# espJhon.net
KiCad netlist of a schematic drawn in EAGLE
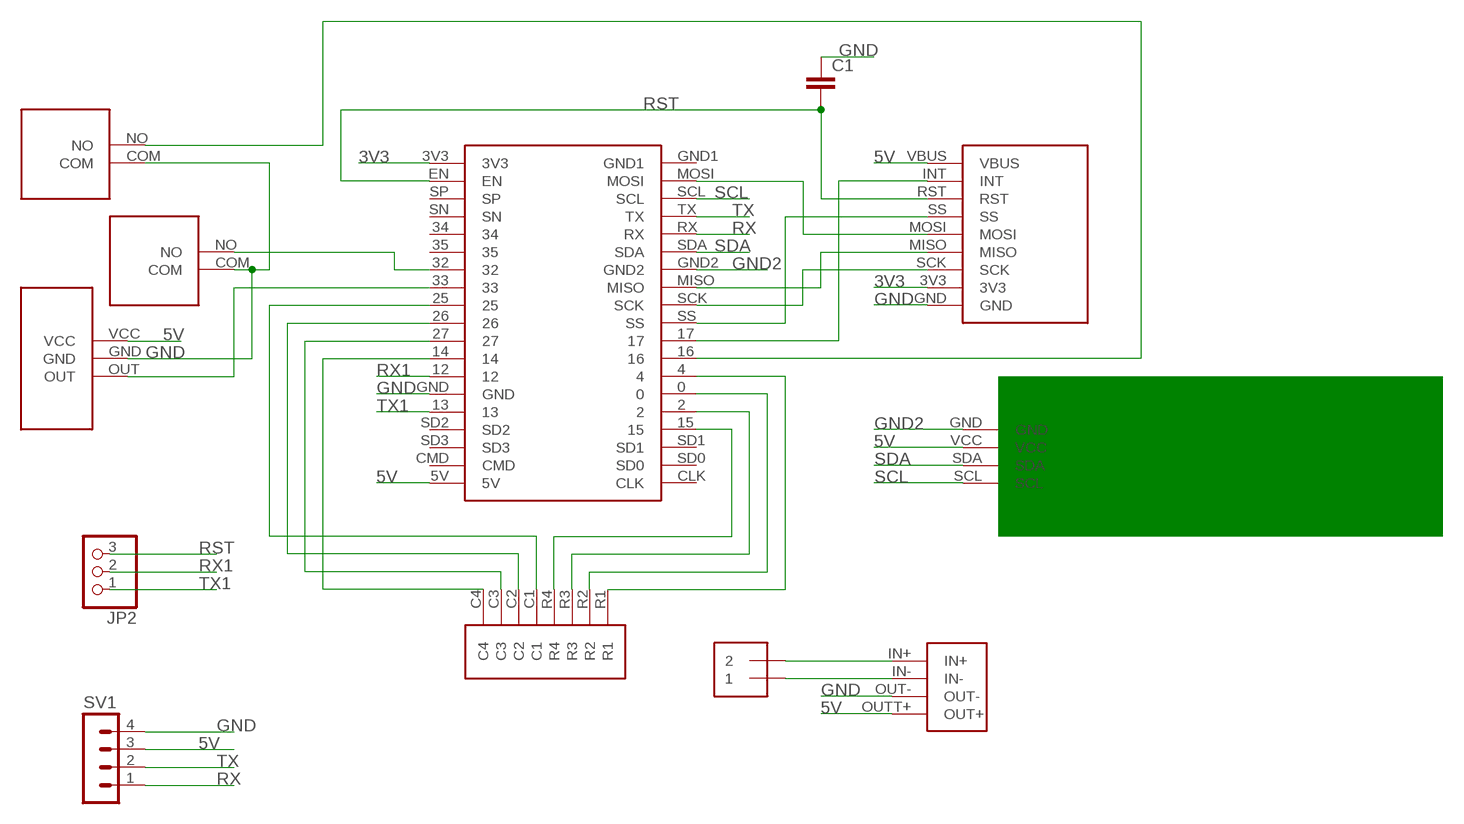
[diagram p0: schematic, sheet 1]

(export (version "E")
  (design (tool "Eeschema 10.0.6"))
  (components
    (comp (ref "C1")
      (value "C2.5/6")
      (footprint "eagle-import:C2.5-6")
      (libsource (lib "eagle-import") (part "C2.5/6"))
    )
    (comp (ref "J1")
      (value "1X2-3.5MM")
      (footprint "eagle-import:1X2-3.5MM")
      (libsource (lib "eagle-import") (part "1X2-3.5MM"))
    )
    (comp (ref "JP2")
      (value "PINHD-1X3")
      (footprint "eagle-import:1X03")
      (libsource (lib "eagle-import") (part "PINHD-1X3"))
    )
    (comp (ref "SV1")
      (value "MA04-1")
      (footprint "eagle-import:MA04-1")
      (libsource (lib "eagle-import") (part "MA04-1"))
    )
    (comp (ref "U$1")
      (value "XL4005E1")
      (footprint "eagle-import:XL4005E1")
      (libsource (lib "eagle-import") (part "XL4005E1"))
    )
    (comp (ref "U$2")
      (value "USB_HOST")
      (footprint "eagle-import:USB_HOST")
      (libsource (lib "eagle-import") (part "USB_HOST"))
    )
    (comp (ref "U$3")
      (value "ESP32_NEW")
      (footprint "eagle-import:ESP32_NEW")
      (libsource (lib "eagle-import") (part "ESP32_NEW"))
    )
    (comp (ref "U$4")
      (value "KEYPAD_4X4")
      (footprint "eagle-import:KEYPAD_4X4")
      (libsource (lib "eagle-import") (part "KEYPAD_4X4"))
    )
    (comp (ref "U$6")
      (value "LCD_I2C")
      (footprint "eagle-import:LCD_I2C")
      (libsource (lib "eagle-import") (part "LCD_I2C"))
    )
    (comp (ref "U$7")
      (value "IR_SENSOR")
      (footprint "eagle-import:IR_SENSOR")
      (libsource (lib "eagle-import") (part "IR_SENSOR"))
    )
    (comp (ref "U$8")
      (value "SWITCHLIMITER")
      (footprint "eagle-import:SWICHLIMITER")
      (libsource (lib "eagle-import") (part "SWITCHLIMITER"))
    )
    (comp (ref "U$9")
      (value "SWITCHLIMITER")
      (footprint "eagle-import:SWICHLIMITER")
      (libsource (lib "eagle-import") (part "SWITCHLIMITER"))
    )
  )
  (nets
    (net (code "1") (name "/3V3") (class "Default")
      (node (ref "U$2") (pin "3V3") (pinfunction "3V3_3V3") (pintype "bidirectional"))
      (node (ref "U$3") (pin "3V3") (pinfunction "3V3_3V3") (pintype "bidirectional"))
    )
    (net (code "2") (name "/5V") (class "Default")
      (node (ref "SV1") (pin "3") (pinfunction "3_3") (pintype "passive"))
      (node (ref "U$1") (pin "OUTT+") (pinfunction "OUT+_OUTT+") (pintype "bidirectional"))
      (node (ref "U$2") (pin "VBUS") (pinfunction "VBUS_VBUS") (pintype "bidirectional"))
      (node (ref "U$3") (pin "5V") (pinfunction "5V_5V") (pintype "bidirectional"))
      (node (ref "U$6") (pin "VCC") (pinfunction "VCC_VCC") (pintype "bidirectional"))
      (node (ref "U$7") (pin "VCC") (pinfunction "VCC_VCC") (pintype "bidirectional"))
    )
    (net (code "3") (name "/GND") (class "Default")
      (node (ref "C1") (pin "1") (pinfunction "1_1") (pintype "passive"))
      (node (ref "SV1") (pin "4") (pinfunction "4_4") (pintype "passive"))
      (node (ref "U$1") (pin "OUT-") (pinfunction "OUT-_OUT-") (pintype "bidirectional"))
      (node (ref "U$2") (pin "GND") (pinfunction "GND_GND") (pintype "bidirectional"))
      (node (ref "U$3") (pin "GND") (pinfunction "GND_GND") (pintype "bidirectional"))
      (node (ref "U$7") (pin "GND") (pinfunction "GND_GND") (pintype "bidirectional"))
      (node (ref "U$8") (pin "COM") (pinfunction "COM_COM") (pintype "bidirectional"))
      (node (ref "U$9") (pin "COM") (pinfunction "COM_COM") (pintype "bidirectional"))
    )
    (net (code "4") (name "/GND2") (class "Default")
      (node (ref "U$3") (pin "GND2") (pinfunction "GND2_GND2") (pintype "bidirectional"))
      (node (ref "U$6") (pin "GND") (pinfunction "GND_GND") (pintype "bidirectional"))
    )
    (net (code "5") (name "/RST") (class "Default")
      (node (ref "C1") (pin "2") (pinfunction "2_2") (pintype "passive"))
      (node (ref "JP2") (pin "3") (pinfunction "3_3") (pintype "passive"))
      (node (ref "U$2") (pin "RST") (pinfunction "RST_RST") (pintype "bidirectional"))
      (node (ref "U$3") (pin "EN") (pinfunction "EN_EN") (pintype "bidirectional"))
    )
    (net (code "6") (name "/RX") (class "Default")
      (node (ref "SV1") (pin "1") (pinfunction "1_1") (pintype "passive"))
      (node (ref "U$3") (pin "RX") (pinfunction "RX_RX") (pintype "bidirectional"))
    )
    (net (code "7") (name "/RX1") (class "Default")
      (node (ref "JP2") (pin "2") (pinfunction "2_2") (pintype "passive"))
      (node (ref "U$3") (pin "12") (pinfunction "12_12") (pintype "bidirectional"))
    )
    (net (code "8") (name "/SCL") (class "Default")
      (node (ref "U$3") (pin "SCL") (pinfunction "SCL_SCL") (pintype "bidirectional"))
      (node (ref "U$6") (pin "SCL") (pinfunction "SCL_SCL") (pintype "bidirectional"))
    )
    (net (code "9") (name "/SDA") (class "Default")
      (node (ref "U$3") (pin "SDA") (pinfunction "SDA_SDA") (pintype "bidirectional"))
      (node (ref "U$6") (pin "SDA") (pinfunction "SDA_SDA") (pintype "bidirectional"))
    )
    (net (code "10") (name "/TX") (class "Default")
      (node (ref "SV1") (pin "2") (pinfunction "2_2") (pintype "passive"))
      (node (ref "U$3") (pin "TX") (pinfunction "TX_TX") (pintype "bidirectional"))
    )
    (net (code "11") (name "/TX1") (class "Default")
      (node (ref "JP2") (pin "1") (pinfunction "1_1") (pintype "passive"))
      (node (ref "U$3") (pin "13") (pinfunction "13_13") (pintype "bidirectional"))
    )
    (net (code "12") (name "Net-(J1-Pad1)") (class "Default")
      (node (ref "J1") (pin "1") (pinfunction "1_1") (pintype "passive"))
      (node (ref "U$1") (pin "IN-") (pinfunction "IN-_IN-") (pintype "bidirectional"))
    )
    (net (code "13") (name "Net-(J1-Pad2)") (class "Default")
      (node (ref "J1") (pin "2") (pinfunction "2_2") (pintype "passive"))
      (node (ref "U$1") (pin "IN+") (pinfunction "IN+_IN+") (pintype "bidirectional"))
    )
    (net (code "14") (name "Net-(U$2-PadINT)") (class "Default")
      (node (ref "U$2") (pin "INT") (pinfunction "INT_INT") (pintype "bidirectional"))
      (node (ref "U$3") (pin "17") (pinfunction "17_17") (pintype "bidirectional"))
    )
    (net (code "15") (name "Net-(U$2-PadMISO)") (class "Default")
      (node (ref "U$2") (pin "MISO") (pinfunction "MISO_MISO") (pintype "bidirectional"))
      (node (ref "U$3") (pin "MISO") (pinfunction "MISO_MISO") (pintype "bidirectional"))
    )
    (net (code "16") (name "Net-(U$2-PadMOSI)") (class "Default")
      (node (ref "U$2") (pin "MOSI") (pinfunction "MOSI_MOSI") (pintype "bidirectional"))
      (node (ref "U$3") (pin "MOSI") (pinfunction "MOSI_MOSI") (pintype "bidirectional"))
    )
    (net (code "17") (name "Net-(U$2-PadSCK)") (class "Default")
      (node (ref "U$2") (pin "SCK") (pinfunction "SCK_SCK") (pintype "bidirectional"))
      (node (ref "U$3") (pin "SCK") (pinfunction "SCK_SCK") (pintype "bidirectional"))
    )
    (net (code "18") (name "Net-(U$2-PadSS)") (class "Default")
      (node (ref "U$2") (pin "SS") (pinfunction "SS_SS") (pintype "bidirectional"))
      (node (ref "U$3") (pin "SS") (pinfunction "SS_SS") (pintype "bidirectional"))
    )
    (net (code "19") (name "Net-(U$3-Pad0)") (class "Default")
      (node (ref "U$3") (pin "0") (pinfunction "0_0") (pintype "bidirectional"))
      (node (ref "U$4") (pin "R2") (pinfunction "R2_R2") (pintype "bidirectional"))
    )
    (net (code "20") (name "Net-(U$3-Pad2)") (class "Default")
      (node (ref "U$3") (pin "2") (pinfunction "2_2") (pintype "bidirectional"))
      (node (ref "U$4") (pin "R3") (pinfunction "R3_R3") (pintype "bidirectional"))
    )
    (net (code "21") (name "Net-(U$3-Pad4)") (class "Default")
      (node (ref "U$3") (pin "4") (pinfunction "4_4") (pintype "bidirectional"))
      (node (ref "U$4") (pin "R1") (pinfunction "R1_R1") (pintype "bidirectional"))
    )
    (net (code "22") (name "Net-(U$3-Pad14)") (class "Default")
      (node (ref "U$3") (pin "14") (pinfunction "14_14") (pintype "bidirectional"))
      (node (ref "U$4") (pin "C4") (pinfunction "C4_C4") (pintype "bidirectional"))
    )
    (net (code "23") (name "Net-(U$3-Pad15)") (class "Default")
      (node (ref "U$3") (pin "15") (pinfunction "15_15") (pintype "bidirectional"))
      (node (ref "U$4") (pin "R4") (pinfunction "R4_R4") (pintype "bidirectional"))
    )
    (net (code "24") (name "Net-(U$3-Pad16)") (class "Default")
      (node (ref "U$3") (pin "16") (pinfunction "16_16") (pintype "bidirectional"))
      (node (ref "U$8") (pin "NO") (pinfunction "NO_NO") (pintype "bidirectional"))
    )
    (net (code "25") (name "Net-(U$3-Pad25)") (class "Default")
      (node (ref "U$3") (pin "25") (pinfunction "25_25") (pintype "bidirectional"))
      (node (ref "U$4") (pin "C1") (pinfunction "C1_C1") (pintype "bidirectional"))
    )
    (net (code "26") (name "Net-(U$3-Pad26)") (class "Default")
      (node (ref "U$3") (pin "26") (pinfunction "26_26") (pintype "bidirectional"))
      (node (ref "U$4") (pin "C2") (pinfunction "C2_C2") (pintype "bidirectional"))
    )
    (net (code "27") (name "Net-(U$3-Pad27)") (class "Default")
      (node (ref "U$3") (pin "27") (pinfunction "27_27") (pintype "bidirectional"))
      (node (ref "U$4") (pin "C3") (pinfunction "C3_C3") (pintype "bidirectional"))
    )
    (net (code "28") (name "Net-(U$3-Pad32)") (class "Default")
      (node (ref "U$3") (pin "32") (pinfunction "32_32") (pintype "bidirectional"))
      (node (ref "U$9") (pin "NO") (pinfunction "NO_NO") (pintype "bidirectional"))
    )
    (net (code "29") (name "Net-(U$3-Pad33)") (class "Default")
      (node (ref "U$3") (pin "33") (pinfunction "33_33") (pintype "bidirectional"))
      (node (ref "U$7") (pin "OUT") (pinfunction "OUT_OUT") (pintype "bidirectional"))
    )
    (net (code "30") (name "unconnected-(U$3-Pad34)") (class "Default")
      (node (ref "U$3") (pin "34") (pinfunction "34_34") (pintype "bidirectional"))
    )
    (net (code "31") (name "unconnected-(U$3-Pad35)") (class "Default")
      (node (ref "U$3") (pin "35") (pinfunction "35_35") (pintype "bidirectional"))
    )
    (net (code "32") (name "unconnected-(U$3-PadCLK)") (class "Default")
      (node (ref "U$3") (pin "CLK") (pinfunction "CLK_CLK") (pintype "bidirectional"))
    )
    (net (code "33") (name "unconnected-(U$3-PadCMD)") (class "Default")
      (node (ref "U$3") (pin "CMD") (pinfunction "CMD_CMD") (pintype "bidirectional"))
    )
    (net (code "34") (name "unconnected-(U$3-PadGND1)") (class "Default")
      (node (ref "U$3") (pin "GND1") (pinfunction "GND1_GND1") (pintype "bidirectional"))
    )
    (net (code "35") (name "unconnected-(U$3-PadSD0)") (class "Default")
      (node (ref "U$3") (pin "SD0") (pinfunction "SD0_SD0") (pintype "bidirectional"))
    )
    (net (code "36") (name "unconnected-(U$3-PadSD1)") (class "Default")
      (node (ref "U$3") (pin "SD1") (pinfunction "SD1_SD1") (pintype "bidirectional"))
    )
    (net (code "37") (name "unconnected-(U$3-PadSD2)") (class "Default")
      (node (ref "U$3") (pin "SD2") (pinfunction "SD2_SD2") (pintype "bidirectional"))
    )
    (net (code "38") (name "unconnected-(U$3-PadSD3)") (class "Default")
      (node (ref "U$3") (pin "SD3") (pinfunction "SD3_SD3") (pintype "bidirectional"))
    )
    (net (code "39") (name "unconnected-(U$3-PadSN)") (class "Default")
      (node (ref "U$3") (pin "SN") (pinfunction "SN_SN") (pintype "bidirectional"))
    )
    (net (code "40") (name "unconnected-(U$3-PadSP)") (class "Default")
      (node (ref "U$3") (pin "SP") (pinfunction "SP_SP") (pintype "bidirectional"))
    )
  )
)
